# input_shield.net
KiCad netlist of a schematic drawn in EAGLE
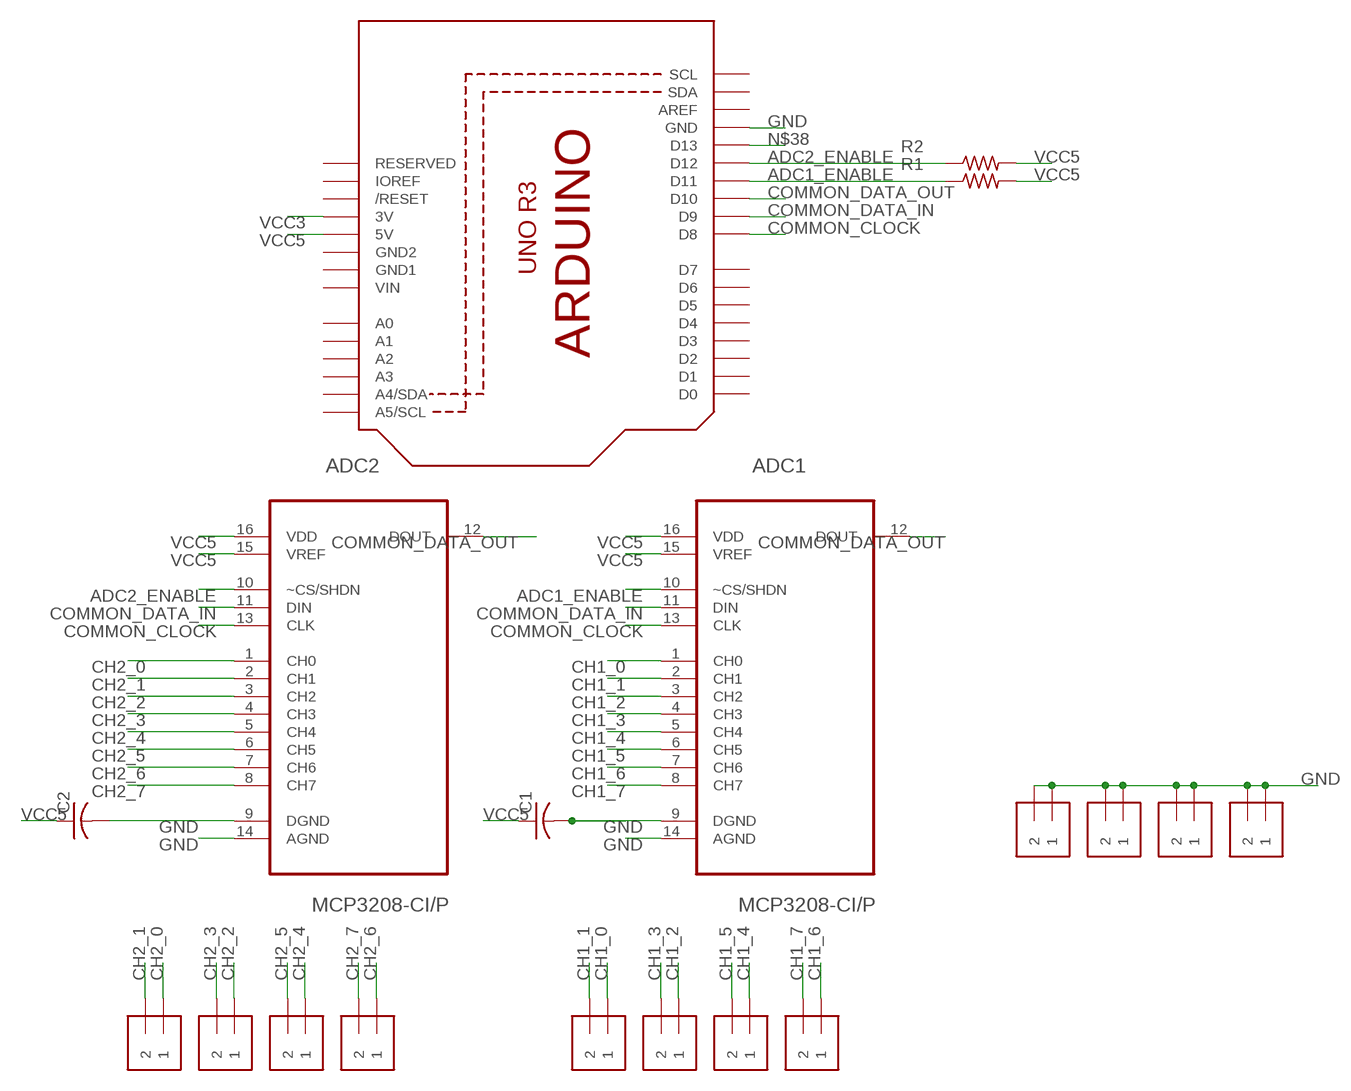
[diagram p0: schematic, sheet 1]

(export (version "E")
  (design (tool "Eeschema 10.0.6"))
  (components
    (comp (ref "ADC1")
      (value "MCP3208-CI/P")
      (footprint "eagle-import:DIP254P762X432-16")
      (libsource (lib "eagle-import") (part "MCP3208-CI/P"))
    )
    (comp (ref "ADC2")
      (value "MCP3208-CI/P")
      (footprint "eagle-import:DIP254P762X432-16")
      (libsource (lib "eagle-import") (part "MCP3208-CI/P"))
    )
    (comp (ref "C1")
      (value "C-US025-025X050")
      (footprint "eagle-import:C025-025X050")
      (libsource (lib "eagle-import") (part "C-US025-025X050"))
    )
    (comp (ref "C2")
      (value "C-US025-025X050")
      (footprint "eagle-import:C025-025X050")
      (libsource (lib "eagle-import") (part "C-US025-025X050"))
    )
    (comp (ref "J1")
      (value "1X2-3.5MM")
      (footprint "eagle-import:1X2-3.5MM")
      (libsource (lib "eagle-import") (part "1X2-3.5MM"))
    )
    (comp (ref "J2")
      (value "1X2-3.5MM")
      (footprint "eagle-import:1X2-3.5MM")
      (libsource (lib "eagle-import") (part "1X2-3.5MM"))
    )
    (comp (ref "J3")
      (value "1X2-3.5MM")
      (footprint "eagle-import:1X2-3.5MM")
      (libsource (lib "eagle-import") (part "1X2-3.5MM"))
    )
    (comp (ref "J4")
      (value "1X2-3.5MM")
      (footprint "eagle-import:1X2-3.5MM")
      (libsource (lib "eagle-import") (part "1X2-3.5MM"))
    )
    (comp (ref "J5")
      (value "1X2-3.5MM")
      (footprint "eagle-import:1X2-3.5MM")
      (libsource (lib "eagle-import") (part "1X2-3.5MM"))
    )
    (comp (ref "J6")
      (value "1X2-3.5MM")
      (footprint "eagle-import:1X2-3.5MM")
      (libsource (lib "eagle-import") (part "1X2-3.5MM"))
    )
    (comp (ref "J7")
      (value "1X2-3.5MM")
      (footprint "eagle-import:1X2-3.5MM")
      (libsource (lib "eagle-import") (part "1X2-3.5MM"))
    )
    (comp (ref "J8")
      (value "1X2-3.5MM")
      (footprint "eagle-import:1X2-3.5MM")
      (libsource (lib "eagle-import") (part "1X2-3.5MM"))
    )
    (comp (ref "J9")
      (value "1X2-3.5MM")
      (footprint "eagle-import:1X2-3.5MM")
      (libsource (lib "eagle-import") (part "1X2-3.5MM"))
    )
    (comp (ref "J10")
      (value "1X2-3.5MM")
      (footprint "eagle-import:1X2-3.5MM")
      (libsource (lib "eagle-import") (part "1X2-3.5MM"))
    )
    (comp (ref "J11")
      (value "1X2-3.5MM")
      (footprint "eagle-import:1X2-3.5MM")
      (libsource (lib "eagle-import") (part "1X2-3.5MM"))
    )
    (comp (ref "J12")
      (value "1X2-3.5MM")
      (footprint "eagle-import:1X2-3.5MM")
      (libsource (lib "eagle-import") (part "1X2-3.5MM"))
    )
    (comp (ref "R1")
      (value "R-US_0204/5")
      (footprint "eagle-import:0204_5")
      (libsource (lib "eagle-import") (part "R-US_0204/5"))
    )
    (comp (ref "R2")
      (value "R-US_0204/5")
      (footprint "eagle-import:0204_5")
      (libsource (lib "eagle-import") (part "R-US_0204/5"))
    )
    (comp (ref "U1")
      (value "ARDUINOR3-DIMENSION")
      (footprint "eagle-import:ARDUINOR3")
      (libsource (lib "eagle-import") (part "ARDUINOR3-DIMENSION"))
    )
  )
  (nets
    (net (code "1") (name "/ADC1_ENABLE") (class "Default")
      (node (ref "ADC1") (pin "10") (pinfunction "~{CS/SHDN}_10") (pintype "input"))
      (node (ref "R1") (pin "1") (pinfunction "1_1") (pintype "passive"))
      (node (ref "U1") (pin "D11") (pinfunction "D11_D11") (pintype "bidirectional"))
    )
    (net (code "2") (name "/ADC2_ENABLE") (class "Default")
      (node (ref "ADC2") (pin "10") (pinfunction "~{CS/SHDN}_10") (pintype "input"))
      (node (ref "R2") (pin "1") (pinfunction "1_1") (pintype "passive"))
      (node (ref "U1") (pin "D12") (pinfunction "D12_D12") (pintype "bidirectional"))
    )
    (net (code "3") (name "/CH1_0") (class "Default")
      (node (ref "ADC1") (pin "1") (pinfunction "CH0_1") (pintype "input"))
      (node (ref "J5") (pin "1") (pinfunction "1_1") (pintype "passive"))
    )
    (net (code "4") (name "/CH1_1") (class "Default")
      (node (ref "ADC1") (pin "2") (pinfunction "CH1_2") (pintype "input"))
      (node (ref "J5") (pin "2") (pinfunction "2_2") (pintype "passive"))
    )
    (net (code "5") (name "/CH1_2") (class "Default")
      (node (ref "ADC1") (pin "3") (pinfunction "CH2_3") (pintype "input"))
      (node (ref "J6") (pin "1") (pinfunction "1_1") (pintype "passive"))
    )
    (net (code "6") (name "/CH1_3") (class "Default")
      (node (ref "ADC1") (pin "4") (pinfunction "CH3_4") (pintype "input"))
      (node (ref "J6") (pin "2") (pinfunction "2_2") (pintype "passive"))
    )
    (net (code "7") (name "/CH1_4") (class "Default")
      (node (ref "ADC1") (pin "5") (pinfunction "CH4_5") (pintype "input"))
      (node (ref "J7") (pin "1") (pinfunction "1_1") (pintype "passive"))
    )
    (net (code "8") (name "/CH1_5") (class "Default")
      (node (ref "ADC1") (pin "6") (pinfunction "CH5_6") (pintype "input"))
      (node (ref "J7") (pin "2") (pinfunction "2_2") (pintype "passive"))
    )
    (net (code "9") (name "/CH1_6") (class "Default")
      (node (ref "ADC1") (pin "7") (pinfunction "CH6_7") (pintype "input"))
      (node (ref "J8") (pin "1") (pinfunction "1_1") (pintype "passive"))
    )
    (net (code "10") (name "/CH1_7") (class "Default")
      (node (ref "ADC1") (pin "8") (pinfunction "CH7_8") (pintype "input"))
      (node (ref "J8") (pin "2") (pinfunction "2_2") (pintype "passive"))
    )
    (net (code "11") (name "/CH2_0") (class "Default")
      (node (ref "ADC2") (pin "1") (pinfunction "CH0_1") (pintype "input"))
      (node (ref "J1") (pin "1") (pinfunction "1_1") (pintype "passive"))
    )
    (net (code "12") (name "/CH2_1") (class "Default")
      (node (ref "ADC2") (pin "2") (pinfunction "CH1_2") (pintype "input"))
      (node (ref "J1") (pin "2") (pinfunction "2_2") (pintype "passive"))
    )
    (net (code "13") (name "/CH2_2") (class "Default")
      (node (ref "ADC2") (pin "3") (pinfunction "CH2_3") (pintype "input"))
      (node (ref "J2") (pin "1") (pinfunction "1_1") (pintype "passive"))
    )
    (net (code "14") (name "/CH2_3") (class "Default")
      (node (ref "ADC2") (pin "4") (pinfunction "CH3_4") (pintype "input"))
      (node (ref "J2") (pin "2") (pinfunction "2_2") (pintype "passive"))
    )
    (net (code "15") (name "/CH2_4") (class "Default")
      (node (ref "ADC2") (pin "5") (pinfunction "CH4_5") (pintype "input"))
      (node (ref "J3") (pin "1") (pinfunction "1_1") (pintype "passive"))
    )
    (net (code "16") (name "/CH2_5") (class "Default")
      (node (ref "ADC2") (pin "6") (pinfunction "CH5_6") (pintype "input"))
      (node (ref "J3") (pin "2") (pinfunction "2_2") (pintype "passive"))
    )
    (net (code "17") (name "/CH2_6") (class "Default")
      (node (ref "ADC2") (pin "7") (pinfunction "CH6_7") (pintype "input"))
      (node (ref "J4") (pin "1") (pinfunction "1_1") (pintype "passive"))
    )
    (net (code "18") (name "/CH2_7") (class "Default")
      (node (ref "ADC2") (pin "8") (pinfunction "CH7_8") (pintype "input"))
      (node (ref "J4") (pin "2") (pinfunction "2_2") (pintype "passive"))
    )
    (net (code "19") (name "/COMMON_CLOCK") (class "Default")
      (node (ref "ADC1") (pin "13") (pinfunction "CLK_13") (pintype "input"))
      (node (ref "ADC2") (pin "13") (pinfunction "CLK_13") (pintype "input"))
      (node (ref "U1") (pin "D8") (pinfunction "D8_D8") (pintype "bidirectional"))
    )
    (net (code "20") (name "/COMMON_DATA_IN") (class "Default")
      (node (ref "ADC1") (pin "11") (pinfunction "DIN_11") (pintype "input"))
      (node (ref "ADC2") (pin "11") (pinfunction "DIN_11") (pintype "input"))
      (node (ref "U1") (pin "D9") (pinfunction "D9_D9") (pintype "bidirectional"))
    )
    (net (code "21") (name "/COMMON_DATA_OUT") (class "Default")
      (node (ref "ADC1") (pin "12") (pinfunction "DOUT_12") (pintype "output"))
      (node (ref "ADC2") (pin "12") (pinfunction "DOUT_12") (pintype "output"))
      (node (ref "U1") (pin "D10") (pinfunction "D10_D10") (pintype "bidirectional"))
    )
    (net (code "22") (name "/GND") (class "Default")
      (node (ref "ADC1") (pin "14") (pinfunction "AGND_14") (pintype "passive"))
      (node (ref "ADC1") (pin "9") (pinfunction "DGND_9") (pintype "passive"))
      (node (ref "ADC2") (pin "14") (pinfunction "AGND_14") (pintype "passive"))
      (node (ref "ADC2") (pin "9") (pinfunction "DGND_9") (pintype "passive"))
      (node (ref "C1") (pin "2") (pinfunction "2_2") (pintype "passive"))
      (node (ref "C2") (pin "2") (pinfunction "2_2") (pintype "passive"))
      (node (ref "J10") (pin "1") (pinfunction "1_1") (pintype "passive"))
      (node (ref "J10") (pin "2") (pinfunction "2_2") (pintype "passive"))
      (node (ref "J11") (pin "1") (pinfunction "1_1") (pintype "passive"))
      (node (ref "J11") (pin "2") (pinfunction "2_2") (pintype "passive"))
      (node (ref "J12") (pin "1") (pinfunction "1_1") (pintype "passive"))
      (node (ref "J12") (pin "2") (pinfunction "2_2") (pintype "passive"))
      (node (ref "J9") (pin "1") (pinfunction "1_1") (pintype "passive"))
      (node (ref "J9") (pin "2") (pinfunction "2_2") (pintype "passive"))
      (node (ref "U1") (pin "GND") (pinfunction "GND_GND") (pintype "power_in"))
    )
    (net (code "23") (name "/GND1") (class "Default")
      (node (ref "U1") (pin "GND1") (pinfunction "GND1_GND1") (pintype "power_in"))
    )
    (net (code "24") (name "/GND2") (class "Default")
      (node (ref "U1") (pin "GND2") (pinfunction "GND2_GND2") (pintype "power_in"))
    )
    (net (code "25") (name "/N$38") (class "Default")
      (node (ref "U1") (pin "D13") (pinfunction "D13_D13") (pintype "bidirectional"))
    )
    (net (code "26") (name "/VCC3") (class "Default")
      (node (ref "U1") (pin "3V") (pinfunction "3V_3V") (pintype "power_in"))
    )
    (net (code "27") (name "/VCC5") (class "Default")
      (node (ref "ADC1") (pin "15") (pinfunction "VREF_15") (pintype "power_in"))
      (node (ref "ADC1") (pin "16") (pinfunction "VDD_16") (pintype "power_in"))
      (node (ref "ADC2") (pin "15") (pinfunction "VREF_15") (pintype "power_in"))
      (node (ref "ADC2") (pin "16") (pinfunction "VDD_16") (pintype "power_in"))
      (node (ref "C1") (pin "1") (pinfunction "1_1") (pintype "passive"))
      (node (ref "C2") (pin "1") (pinfunction "1_1") (pintype "passive"))
      (node (ref "R1") (pin "2") (pinfunction "2_2") (pintype "passive"))
      (node (ref "R2") (pin "2") (pinfunction "2_2") (pintype "passive"))
      (node (ref "U1") (pin "5V") (pinfunction "5V_5V") (pintype "power_in"))
    )
    (net (code "28") (name "/VIN") (class "Default")
      (node (ref "U1") (pin "VIN") (pinfunction "VIN_VIN") (pintype "power_in"))
    )
    (net (code "29") (name "unconnected-(U1-A4{slash}SDA-PadA4)") (class "Default")
      (node (ref "U1") (pin "A4") (pinfunction "A4/SDA_A4") (pintype "bidirectional"))
    )
    (net (code "30") (name "unconnected-(U1-A5{slash}SCL-PadA5)") (class "Default")
      (node (ref "U1") (pin "A5") (pinfunction "A5/SCL_A5") (pintype "bidirectional"))
    )
    (net (code "31") (name "unconnected-(U1-PadA0)") (class "Default")
      (node (ref "U1") (pin "A0") (pinfunction "A0_A0") (pintype "bidirectional"))
    )
    (net (code "32") (name "unconnected-(U1-PadA1)") (class "Default")
      (node (ref "U1") (pin "A1") (pinfunction "A1_A1") (pintype "bidirectional"))
    )
    (net (code "33") (name "unconnected-(U1-PadA2)") (class "Default")
      (node (ref "U1") (pin "A2") (pinfunction "A2_A2") (pintype "bidirectional"))
    )
    (net (code "34") (name "unconnected-(U1-PadA3)") (class "Default")
      (node (ref "U1") (pin "A3") (pinfunction "A3_A3") (pintype "bidirectional"))
    )
    (net (code "35") (name "unconnected-(U1-PadAREF)") (class "Default")
      (node (ref "U1") (pin "AREF") (pinfunction "AREF_AREF") (pintype "bidirectional"))
    )
    (net (code "36") (name "unconnected-(U1-PadD0)") (class "Default")
      (node (ref "U1") (pin "D0") (pinfunction "D0_D0") (pintype "bidirectional"))
    )
    (net (code "37") (name "unconnected-(U1-PadD1)") (class "Default")
      (node (ref "U1") (pin "D1") (pinfunction "D1_D1") (pintype "bidirectional"))
    )
    (net (code "38") (name "unconnected-(U1-PadD2)") (class "Default")
      (node (ref "U1") (pin "D2") (pinfunction "D2_D2") (pintype "bidirectional"))
    )
    (net (code "39") (name "unconnected-(U1-PadD3)") (class "Default")
      (node (ref "U1") (pin "D3") (pinfunction "D3_D3") (pintype "bidirectional"))
    )
    (net (code "40") (name "unconnected-(U1-PadD4)") (class "Default")
      (node (ref "U1") (pin "D4") (pinfunction "D4_D4") (pintype "bidirectional"))
    )
    (net (code "41") (name "unconnected-(U1-PadD5)") (class "Default")
      (node (ref "U1") (pin "D5") (pinfunction "D5_D5") (pintype "bidirectional"))
    )
    (net (code "42") (name "unconnected-(U1-PadD6)") (class "Default")
      (node (ref "U1") (pin "D6") (pinfunction "D6_D6") (pintype "bidirectional"))
    )
    (net (code "43") (name "unconnected-(U1-PadD7)") (class "Default")
      (node (ref "U1") (pin "D7") (pinfunction "D7_D7") (pintype "bidirectional"))
    )
    (net (code "44") (name "unconnected-(U1-PadIOREF)") (class "Default")
      (node (ref "U1") (pin "IOREF") (pinfunction "IOREF_IOREF") (pintype "output"))
    )
    (net (code "45") (name "unconnected-(U1-PadRESERVED)") (class "Default")
      (node (ref "U1") (pin "RESERVED") (pinfunction "RESERVED_RESERVED") (pintype "no_connect"))
    )
    (net (code "46") (name "unconnected-(U1-PadSCL)") (class "Default")
      (node (ref "U1") (pin "SCL") (pinfunction "SCL_SCL") (pintype "bidirectional"))
    )
    (net (code "47") (name "unconnected-(U1-PadSDA)") (class "Default")
      (node (ref "U1") (pin "SDA") (pinfunction "SDA_SDA") (pintype "bidirectional"))
    )
    (net (code "48") (name "unconnected-(U1-{slash}RESET-PadRESET)") (class "Default")
      (node (ref "U1") (pin "RESET") (pinfunction "/RESET_RESET") (pintype "bidirectional"))
    )
  )
)
